# S.net
KiCad netlist of a schematic drawn in Altium Designer
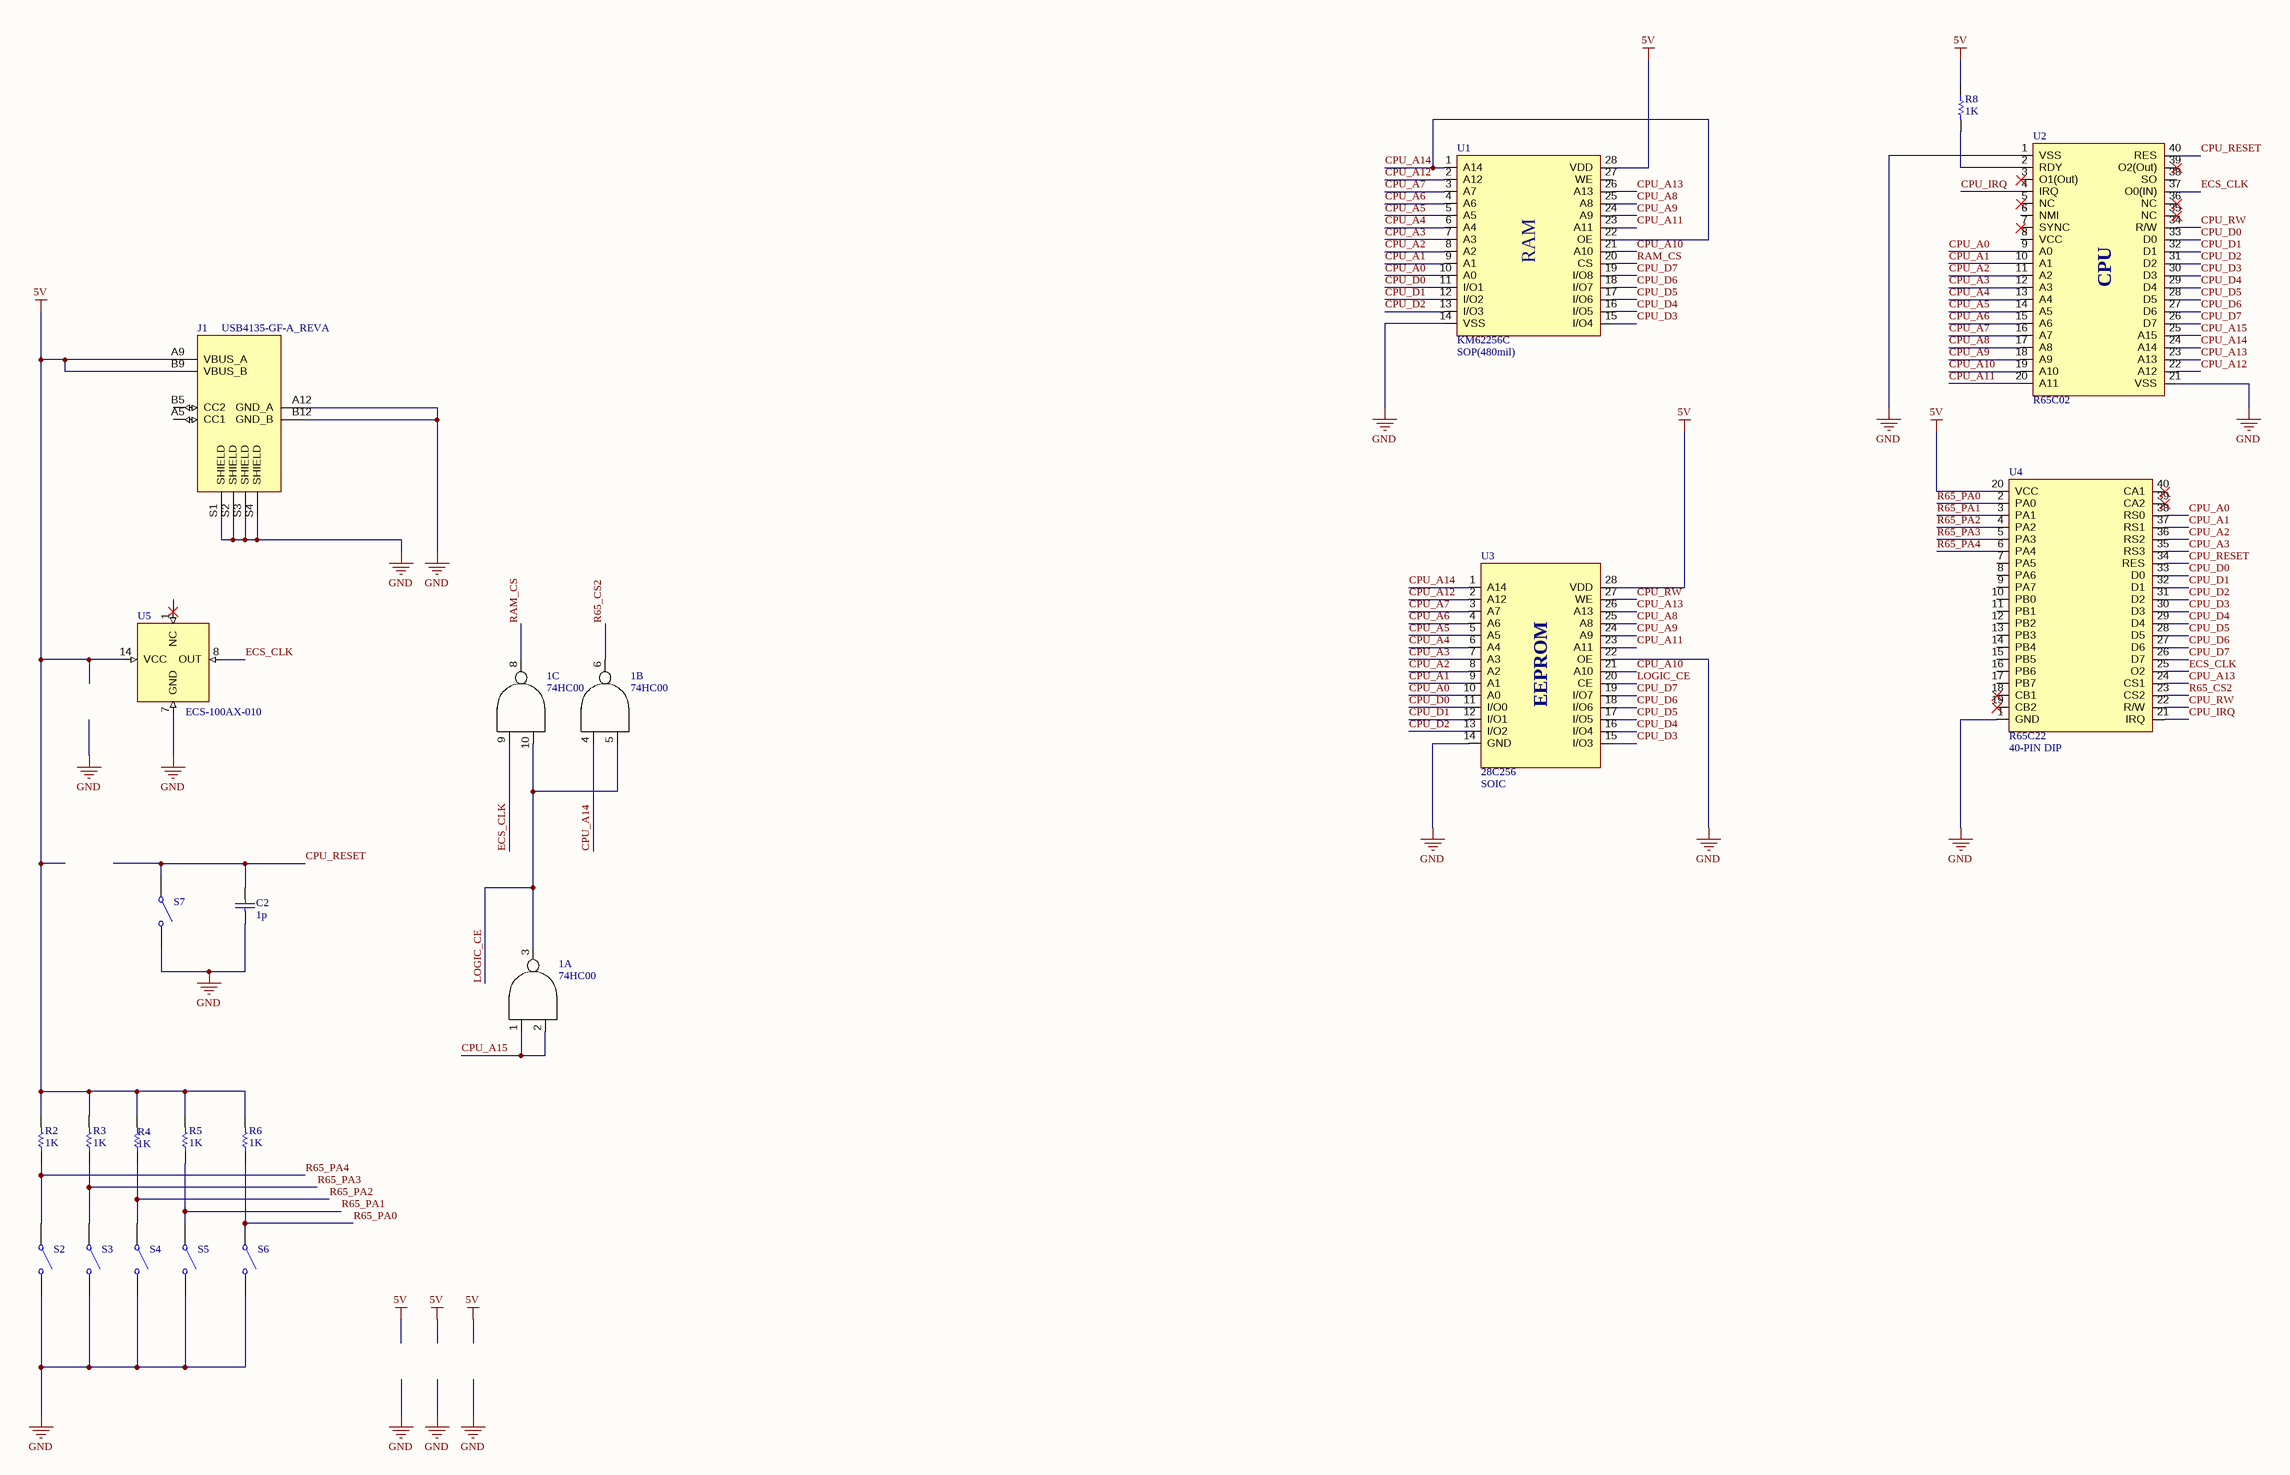
[diagram p0: S.SchDoc]

(export (version "E")
  (design (tool "Eeschema 10.0.6"))
  (components
    (comp (ref "1")
      (value "74HC00")
      (footprint "SOIC127P600X155-14N")
      (description "Quad 2-Input NAND Gate")
      (libsource (lib "") (part "MM74HC00_2"))
    )
    (comp (ref "C2")
      (value "1p")
      (description "Capacitor")
      (libsource (lib "Simulation Generic Components") (part "Capacitor"))
    )
    (comp (ref "J1")
      (value "USB4135-GF-A_REVA")
      (footprint "GCT_USB4135-GF-A_REVA")
      (description "Type C Receptacle, Horizontal, SMT, For Power Charging Only")
      (fields (field (name "MP") "USB4135-GF-A") (field (name "MF") "Global Connector Technology"))
      (libsource (lib "Slib") (part "USB4135-GF-A_REVA"))
    )
    (comp (ref "R2")
      (value "1K")
      (description "Resistor")
      (libsource (lib "Simulation Generic Components") (part "Resistor"))
    )
    (comp (ref "R3")
      (value "1K")
      (description "Resistor")
      (libsource (lib "Simulation Generic Components") (part "Resistor"))
    )
    (comp (ref "R4")
      (value "1K")
      (description "Resistor")
      (libsource (lib "Simulation Generic Components") (part "Resistor"))
    )
    (comp (ref "R5")
      (value "1K")
      (description "Resistor")
      (libsource (lib "Simulation Generic Components") (part "Resistor"))
    )
    (comp (ref "R6")
      (value "1K")
      (description "Resistor")
      (libsource (lib "Simulation Generic Components") (part "Resistor"))
    )
    (comp (ref "R8")
      (value "1K")
      (description "Resistor")
      (libsource (lib "Simulation Generic Components") (part "Resistor"))
    )
    (comp (ref "S2")
      (value "Single-Pole, Single-Throw Switch")
      (libsource (lib "Simulation Generic Components") (part "SPST SW"))
    )
    (comp (ref "S3")
      (value "Single-Pole, Single-Throw Switch")
      (libsource (lib "Simulation Generic Components") (part "SPST SW"))
    )
    (comp (ref "S4")
      (value "Single-Pole, Single-Throw Switch")
      (libsource (lib "Simulation Generic Components") (part "SPST SW"))
    )
    (comp (ref "S5")
      (value "Single-Pole, Single-Throw Switch")
      (libsource (lib "Simulation Generic Components") (part "SPST SW"))
    )
    (comp (ref "S6")
      (value "Single-Pole, Single-Throw Switch")
      (libsource (lib "Simulation Generic Components") (part "SPST SW"))
    )
    (comp (ref "S7")
      (value "Single-Pole, Single-Throw Switch")
      (libsource (lib "Simulation Generic Components") (part "SPST SW"))
    )
    (comp (ref "U1")
      (value "KM62256C")
      (footprint "SOP127P1200X279-28N")
      (description "32Kx8 bit Low Power CMOS Static RAM")
      (fields (field (name "PACKAGE") "SOP(480mil)"))
      (libsource (lib "Slib") (part "62256"))
    )
    (comp (ref "U2")
      (value "R65C02")
      (footprint "SOJ254P1520X356-40N")
      (description "R65C02 family, 5V input, CPU")
      (libsource (lib "Slib") (part "65C02"))
    )
    (comp (ref "U3")
      (value "28C256")
      (footprint "SOIC127P1030X255-28N")
      (description "EEPROM memory; 32kx8bit; 4.5÷5.5V; DIP28; parallel")
      (fields (field (name "PACKAGE") "SOIC"))
      (libsource (lib "Slib") (part "28C256"))
    )
    (comp (ref "U4")
      (value "R65C22")
      (footprint "SOJ254P1520X356-40N")
      (description "8-bit I/O control device")
      (fields (field (name "PACKAGE") "40-PIN DIP"))
      (libsource (lib "Slib") (part "R65C22"))
    )
    (comp (ref "U5")
      (value "ECS-100AX-010")
      (footprint "Oscillator")
      (description "Standard Clock Oscillators DIP-14 5V 1MHz")
      (libsource (lib "Slib") (part "ECS-100AX-010"))
    )
  )
  (nets
    (net (code "1") (name "/CPU_A0") (class "Default")
      (node (ref "U1") (pin "10") (pinfunction "A0_10") (pintype "passive"))
      (node (ref "U2") (pin "9") (pinfunction "A0_9") (pintype "passive"))
      (node (ref "U3") (pin "10") (pinfunction "A0_10") (pintype "passive"))
      (node (ref "U4") (pin "38") (pinfunction "RS0_38") (pintype "passive"))
    )
    (net (code "2") (name "/CPU_A1") (class "Default")
      (node (ref "U1") (pin "9") (pinfunction "A1_9") (pintype "passive"))
      (node (ref "U2") (pin "10") (pinfunction "A1_10") (pintype "passive"))
      (node (ref "U3") (pin "9") (pinfunction "A1_9") (pintype "passive"))
      (node (ref "U4") (pin "37") (pinfunction "RS1_37") (pintype "passive"))
    )
    (net (code "3") (name "/CPU_A2") (class "Default")
      (node (ref "U1") (pin "8") (pinfunction "A2_8") (pintype "passive"))
      (node (ref "U2") (pin "11") (pinfunction "A2_11") (pintype "passive"))
      (node (ref "U3") (pin "8") (pinfunction "A2_8") (pintype "passive"))
      (node (ref "U4") (pin "36") (pinfunction "RS2_36") (pintype "passive"))
    )
    (net (code "4") (name "/CPU_A3") (class "Default")
      (node (ref "U1") (pin "7") (pinfunction "A3_7") (pintype "passive"))
      (node (ref "U2") (pin "12") (pinfunction "A3_12") (pintype "passive"))
      (node (ref "U3") (pin "7") (pinfunction "A3_7") (pintype "passive"))
      (node (ref "U4") (pin "35") (pinfunction "RS3_35") (pintype "passive"))
    )
    (net (code "5") (name "/CPU_A4") (class "Default")
      (node (ref "U1") (pin "6") (pinfunction "A4_6") (pintype "passive"))
      (node (ref "U2") (pin "13") (pinfunction "A4_13") (pintype "passive"))
      (node (ref "U3") (pin "6") (pinfunction "A4_6") (pintype "passive"))
    )
    (net (code "6") (name "/CPU_A5") (class "Default")
      (node (ref "U1") (pin "5") (pinfunction "A5_5") (pintype "passive"))
      (node (ref "U2") (pin "14") (pinfunction "A5_14") (pintype "passive"))
      (node (ref "U3") (pin "5") (pinfunction "A5_5") (pintype "passive"))
    )
    (net (code "7") (name "/CPU_A6") (class "Default")
      (node (ref "U1") (pin "4") (pinfunction "A6_4") (pintype "passive"))
      (node (ref "U2") (pin "15") (pinfunction "A6_15") (pintype "passive"))
      (node (ref "U3") (pin "4") (pinfunction "A6_4") (pintype "passive"))
    )
    (net (code "8") (name "/CPU_A7") (class "Default")
      (node (ref "U1") (pin "3") (pinfunction "A7_3") (pintype "passive"))
      (node (ref "U2") (pin "16") (pinfunction "A7_16") (pintype "passive"))
      (node (ref "U3") (pin "3") (pinfunction "A7_3") (pintype "passive"))
    )
    (net (code "9") (name "/CPU_A8") (class "Default")
      (node (ref "U1") (pin "25") (pinfunction "A8_25") (pintype "passive"))
      (node (ref "U2") (pin "17") (pinfunction "A8_17") (pintype "passive"))
      (node (ref "U3") (pin "25") (pinfunction "A8_25") (pintype "open_emitter"))
    )
    (net (code "10") (name "/CPU_A9") (class "Default")
      (node (ref "U1") (pin "24") (pinfunction "A9_24") (pintype "passive"))
      (node (ref "U2") (pin "18") (pinfunction "A9_18") (pintype "passive"))
      (node (ref "U3") (pin "24") (pinfunction "A9_24") (pintype "open_emitter"))
    )
    (net (code "11") (name "/CPU_A10") (class "Default")
      (node (ref "U1") (pin "21") (pinfunction "A10_21") (pintype "passive"))
      (node (ref "U2") (pin "19") (pinfunction "A10_19") (pintype "passive"))
      (node (ref "U3") (pin "21") (pinfunction "A10_21") (pintype "open_emitter"))
    )
    (net (code "12") (name "/CPU_A11") (class "Default")
      (node (ref "U1") (pin "23") (pinfunction "A11_23") (pintype "passive"))
      (node (ref "U2") (pin "20") (pinfunction "A11_20") (pintype "passive"))
      (node (ref "U3") (pin "23") (pinfunction "A11_23") (pintype "open_emitter"))
    )
    (net (code "13") (name "/CPU_A12") (class "Default")
      (node (ref "U1") (pin "2") (pinfunction "A12_2") (pintype "passive"))
      (node (ref "U2") (pin "22") (pinfunction "A12_22") (pintype "passive"))
      (node (ref "U3") (pin "2") (pinfunction "A12_2") (pintype "passive"))
    )
    (net (code "14") (name "/CPU_A13") (class "Default")
      (node (ref "U1") (pin "26") (pinfunction "A13_26") (pintype "passive"))
      (node (ref "U2") (pin "23") (pinfunction "A13_23") (pintype "passive"))
      (node (ref "U3") (pin "26") (pinfunction "A13_26") (pintype "open_emitter"))
      (node (ref "U4") (pin "24") (pinfunction "CS1_24") (pintype "passive"))
    )
    (net (code "15") (name "/CPU_A14") (class "Default")
      (node (ref "1") (pin "4") (pinfunction "A1_4") (pintype "passive"))
      (node (ref "U1") (pin "1") (pinfunction "A14_1") (pintype "passive"))
      (node (ref "U1") (pin "22") (pinfunction "OE_22") (pintype "passive"))
      (node (ref "U2") (pin "24") (pinfunction "A14_24") (pintype "passive"))
      (node (ref "U3") (pin "1") (pinfunction "A14_1") (pintype "passive"))
    )
    (net (code "16") (name "/CPU_A15") (class "Default")
      (node (ref "1") (pin "1") (pinfunction "A1_1") (pintype "passive"))
      (node (ref "1") (pin "2") (pinfunction "B1_2") (pintype "passive"))
      (node (ref "U2") (pin "25") (pinfunction "A15_25") (pintype "passive"))
    )
    (net (code "17") (name "/CPU_D0") (class "Default")
      (node (ref "U1") (pin "11") (pinfunction "I/O1_11") (pintype "passive"))
      (node (ref "U2") (pin "33") (pinfunction "D0_33") (pintype "passive"))
      (node (ref "U3") (pin "11") (pinfunction "I/O0_11") (pintype "passive"))
      (node (ref "U4") (pin "33") (pinfunction "D0_33") (pintype "passive"))
    )
    (net (code "18") (name "/CPU_D1") (class "Default")
      (node (ref "U1") (pin "12") (pinfunction "I/O2_12") (pintype "passive"))
      (node (ref "U2") (pin "32") (pinfunction "D1_32") (pintype "passive"))
      (node (ref "U3") (pin "12") (pinfunction "I/O1_12") (pintype "passive"))
      (node (ref "U4") (pin "32") (pinfunction "D1_32") (pintype "passive"))
    )
    (net (code "19") (name "/CPU_D2") (class "Default")
      (node (ref "U1") (pin "13") (pinfunction "I/O3_13") (pintype "passive"))
      (node (ref "U2") (pin "31") (pinfunction "D2_31") (pintype "passive"))
      (node (ref "U3") (pin "13") (pinfunction "I/O2_13") (pintype "passive"))
      (node (ref "U4") (pin "31") (pinfunction "D2_31") (pintype "passive"))
    )
    (net (code "20") (name "/CPU_D3") (class "Default")
      (node (ref "U1") (pin "15") (pinfunction "I/O4_15") (pintype "passive"))
      (node (ref "U2") (pin "30") (pinfunction "D3_30") (pintype "passive"))
      (node (ref "U3") (pin "15") (pinfunction "I/O3_15") (pintype "open_emitter"))
      (node (ref "U4") (pin "30") (pinfunction "D3_30") (pintype "passive"))
    )
    (net (code "21") (name "/CPU_D4") (class "Default")
      (node (ref "U1") (pin "16") (pinfunction "I/O5_16") (pintype "passive"))
      (node (ref "U2") (pin "29") (pinfunction "D4_29") (pintype "passive"))
      (node (ref "U3") (pin "16") (pinfunction "I/O4_16") (pintype "open_emitter"))
      (node (ref "U4") (pin "29") (pinfunction "D4_29") (pintype "passive"))
    )
    (net (code "22") (name "/CPU_D5") (class "Default")
      (node (ref "U1") (pin "17") (pinfunction "I/O6_17") (pintype "passive"))
      (node (ref "U2") (pin "28") (pinfunction "D5_28") (pintype "passive"))
      (node (ref "U3") (pin "17") (pinfunction "I/O5_17") (pintype "open_emitter"))
      (node (ref "U4") (pin "28") (pinfunction "D5_28") (pintype "passive"))
    )
    (net (code "23") (name "/CPU_D6") (class "Default")
      (node (ref "U1") (pin "18") (pinfunction "I/O7_18") (pintype "passive"))
      (node (ref "U2") (pin "27") (pinfunction "D6_27") (pintype "passive"))
      (node (ref "U3") (pin "18") (pinfunction "I/O6_18") (pintype "open_emitter"))
      (node (ref "U4") (pin "27") (pinfunction "D6_27") (pintype "passive"))
    )
    (net (code "24") (name "/CPU_D7") (class "Default")
      (node (ref "U1") (pin "19") (pinfunction "I/O8_19") (pintype "passive"))
      (node (ref "U2") (pin "26") (pinfunction "D7_26") (pintype "passive"))
      (node (ref "U3") (pin "19") (pinfunction "I/O7_19") (pintype "open_emitter"))
      (node (ref "U4") (pin "26") (pinfunction "D7_26") (pintype "passive"))
    )
    (net (code "25") (name "/CPU_IRQ") (class "Default")
      (node (ref "U2") (pin "4") (pinfunction "IRQ_4") (pintype "passive"))
      (node (ref "U4") (pin "21") (pinfunction "IRQ_21") (pintype "passive"))
    )
    (net (code "26") (name "/CPU_RESET") (class "Default")
      (node (ref "C2") (pin "2") (pinfunction "2_2") (pintype "passive"))
      (node (ref "S7") (pin "1") (pinfunction "1_1") (pintype "passive"))
      (node (ref "U2") (pin "40") (pinfunction "RES_40") (pintype "passive"))
      (node (ref "U4") (pin "34") (pinfunction "RES_34") (pintype "passive"))
    )
    (net (code "27") (name "/CPU_RW") (class "Default")
      (node (ref "U2") (pin "34") (pinfunction "R/W_34") (pintype "passive"))
      (node (ref "U3") (pin "27") (pinfunction "WE_27") (pintype "open_emitter"))
      (node (ref "U4") (pin "22") (pinfunction "R/W_22") (pintype "passive"))
    )
    (net (code "28") (name "/ECS_CLK") (class "Default")
      (node (ref "1") (pin "9") (pinfunction "A1_9") (pintype "passive"))
      (node (ref "U2") (pin "37") (pinfunction "O0(IN)_37") (pintype "passive"))
      (node (ref "U4") (pin "25") (pinfunction "O2_25") (pintype "passive"))
      (node (ref "U5") (pin "8") (pinfunction "OUT_8") (pintype "input"))
    )
    (net (code "29") (name "/LOGIC_CE") (class "Default")
      (node (ref "1") (pin "10") (pinfunction "B1_10") (pintype "passive"))
      (node (ref "1") (pin "3") (pinfunction "Y2_3") (pintype "passive"))
      (node (ref "1") (pin "5") (pinfunction "B1_5") (pintype "passive"))
      (node (ref "U3") (pin "20") (pinfunction "CE_20") (pintype "open_emitter"))
    )
    (net (code "30") (name "/R65_CS2") (class "Default")
      (node (ref "1") (pin "6") (pinfunction "Y2_6") (pintype "passive"))
      (node (ref "U4") (pin "23") (pinfunction "CS2_23") (pintype "passive"))
    )
    (net (code "31") (name "/R65_PA0") (class "Default")
      (node (ref "R6") (pin "1") (pinfunction "1_1") (pintype "passive"))
      (node (ref "S6") (pin "1") (pinfunction "1_1") (pintype "passive"))
      (node (ref "U4") (pin "2") (pinfunction "PA0_2") (pintype "passive"))
    )
    (net (code "32") (name "/R65_PA1") (class "Default")
      (node (ref "R5") (pin "1") (pinfunction "1_1") (pintype "passive"))
      (node (ref "S5") (pin "1") (pinfunction "1_1") (pintype "passive"))
      (node (ref "U4") (pin "3") (pinfunction "PA1_3") (pintype "passive"))
    )
    (net (code "33") (name "/R65_PA2") (class "Default")
      (node (ref "R4") (pin "1") (pinfunction "1_1") (pintype "passive"))
      (node (ref "S4") (pin "1") (pinfunction "1_1") (pintype "passive"))
      (node (ref "U4") (pin "4") (pinfunction "PA2_4") (pintype "passive"))
    )
    (net (code "34") (name "/R65_PA3") (class "Default")
      (node (ref "R3") (pin "1") (pinfunction "1_1") (pintype "passive"))
      (node (ref "S3") (pin "1") (pinfunction "1_1") (pintype "passive"))
      (node (ref "U4") (pin "5") (pinfunction "PA3_5") (pintype "passive"))
    )
    (net (code "35") (name "/R65_PA4") (class "Default")
      (node (ref "R2") (pin "1") (pinfunction "1_1") (pintype "passive"))
      (node (ref "S2") (pin "1") (pinfunction "1_1") (pintype "passive"))
      (node (ref "U4") (pin "6") (pinfunction "PA4_6") (pintype "passive"))
    )
    (net (code "36") (name "/RAM_CS") (class "Default")
      (node (ref "1") (pin "8") (pinfunction "Y2_8") (pintype "passive"))
      (node (ref "U1") (pin "20") (pinfunction "CS_20") (pintype "passive"))
    )
    (net (code "37") (name "5V") (class "Default")
      (node (ref "J1") (pin "A9") (pinfunction "VBUS_A_A9") (pintype "power_in"))
      (node (ref "J1") (pin "B9") (pinfunction "VBUS_B_B9") (pintype "power_in"))
      (node (ref "R2") (pin "2") (pinfunction "2_2") (pintype "passive"))
      (node (ref "R3") (pin "2") (pinfunction "2_2") (pintype "passive"))
      (node (ref "R4") (pin "2") (pinfunction "2_2") (pintype "passive"))
      (node (ref "R5") (pin "2") (pinfunction "2_2") (pintype "passive"))
      (node (ref "R6") (pin "2") (pinfunction "2_2") (pintype "passive"))
      (node (ref "R8") (pin "1") (pinfunction "1_1") (pintype "passive"))
      (node (ref "U1") (pin "28") (pinfunction "VDD_28") (pintype "passive"))
      (node (ref "U3") (pin "28") (pinfunction "VDD_28") (pintype "open_emitter"))
      (node (ref "U4") (pin "20") (pinfunction "VCC_20") (pintype "passive"))
      (node (ref "U5") (pin "14") (pinfunction "VCC_14") (pintype "input"))
    )
    (net (code "38") (name "GND") (class "Default")
      (node (ref "C2") (pin "1") (pinfunction "1_1") (pintype "passive"))
      (node (ref "J1") (pin "A12") (pinfunction "GND_A_A12") (pintype "power_in"))
      (node (ref "J1") (pin "B12") (pinfunction "GND_B_B12") (pintype "power_in"))
      (node (ref "J1") (pin "S1") (pinfunction "SHIELD_S1") (pintype "passive"))
      (node (ref "J1") (pin "S2") (pinfunction "SHIELD_S2") (pintype "passive"))
      (node (ref "J1") (pin "S3") (pinfunction "SHIELD_S3") (pintype "passive"))
      (node (ref "J1") (pin "S4") (pinfunction "SHIELD_S4") (pintype "passive"))
      (node (ref "S2") (pin "2") (pinfunction "2_2") (pintype "passive"))
      (node (ref "S3") (pin "2") (pinfunction "2_2") (pintype "passive"))
      (node (ref "S4") (pin "2") (pinfunction "2_2") (pintype "passive"))
      (node (ref "S5") (pin "2") (pinfunction "2_2") (pintype "passive"))
      (node (ref "S6") (pin "2") (pinfunction "2_2") (pintype "passive"))
      (node (ref "S7") (pin "2") (pinfunction "2_2") (pintype "passive"))
      (node (ref "U1") (pin "14") (pinfunction "VSS_14") (pintype "passive"))
      (node (ref "U2") (pin "1") (pinfunction "VSS_1") (pintype "passive"))
      (node (ref "U2") (pin "21") (pinfunction "VSS_21") (pintype "passive"))
      (node (ref "U3") (pin "14") (pinfunction "GND_14") (pintype "passive"))
      (node (ref "U3") (pin "22") (pinfunction "OE_22") (pintype "open_emitter"))
      (node (ref "U4") (pin "1") (pinfunction "GND_1") (pintype "passive"))
      (node (ref "U5") (pin "7") (pinfunction "GND_7") (pintype "input"))
    )
    (net (code "39") (name "Net-(U2-RDY)") (class "Default")
      (node (ref "R8") (pin "2") (pinfunction "2_2") (pintype "passive"))
      (node (ref "U2") (pin "2") (pinfunction "RDY_2") (pintype "passive"))
    )
    (net (code "40") (name "unconnected-(J1-CC1-PadA5)") (class "Default")
      (node (ref "J1") (pin "A5") (pinfunction "CC1_A5") (pintype "bidirectional"))
    )
    (net (code "41") (name "unconnected-(J1-CC2-PadB5)") (class "Default")
      (node (ref "J1") (pin "B5") (pinfunction "CC2_B5") (pintype "bidirectional"))
    )
    (net (code "42") (name "unconnected-(U1-WE-Pad27)") (class "Default")
      (node (ref "U1") (pin "27") (pinfunction "WE_27") (pintype "passive"))
    )
    (net (code "43") (name "unconnected-(U2-NC-Pad5)") (class "Default")
      (node (ref "U2") (pin "5") (pinfunction "NC_5") (pintype "passive+no_connect"))
    )
    (net (code "44") (name "unconnected-(U2-NC-Pad35)") (class "Default")
      (node (ref "U2") (pin "35") (pinfunction "NC_35") (pintype "passive+no_connect"))
    )
    (net (code "45") (name "unconnected-(U2-NC-Pad36)") (class "Default")
      (node (ref "U2") (pin "36") (pinfunction "NC_36") (pintype "passive+no_connect"))
    )
    (net (code "46") (name "unconnected-(U2-NMI-Pad6)") (class "Default")
      (node (ref "U2") (pin "6") (pinfunction "NMI_6") (pintype "passive"))
    )
    (net (code "47") (name "unconnected-(U2-O1(Out)-Pad3)") (class "Default")
      (node (ref "U2") (pin "3") (pinfunction "O1(Out)_3") (pintype "passive+no_connect"))
    )
    (net (code "48") (name "unconnected-(U2-O2(Out)-Pad39)") (class "Default")
      (node (ref "U2") (pin "39") (pinfunction "O2(Out)_39") (pintype "passive+no_connect"))
    )
    (net (code "49") (name "unconnected-(U2-SO-Pad38)") (class "Default")
      (node (ref "U2") (pin "38") (pinfunction "SO_38") (pintype "passive"))
    )
    (net (code "50") (name "unconnected-(U2-SYNC-Pad7)") (class "Default")
      (node (ref "U2") (pin "7") (pinfunction "SYNC_7") (pintype "passive+no_connect"))
    )
    (net (code "51") (name "unconnected-(U2-VCC-Pad8)") (class "Default")
      (node (ref "U2") (pin "8") (pinfunction "VCC_8") (pintype "passive"))
    )
    (net (code "52") (name "unconnected-(U4-CA1-Pad40)") (class "Default")
      (node (ref "U4") (pin "40") (pinfunction "CA1_40") (pintype "passive+no_connect"))
    )
    (net (code "53") (name "unconnected-(U4-CA2-Pad39)") (class "Default")
      (node (ref "U4") (pin "39") (pinfunction "CA2_39") (pintype "passive+no_connect"))
    )
    (net (code "54") (name "unconnected-(U4-CB1-Pad18)") (class "Default")
      (node (ref "U4") (pin "18") (pinfunction "CB1_18") (pintype "passive+no_connect"))
    )
    (net (code "55") (name "unconnected-(U4-CB2-Pad19)") (class "Default")
      (node (ref "U4") (pin "19") (pinfunction "CB2_19") (pintype "passive+no_connect"))
    )
    (net (code "56") (name "unconnected-(U4-PA5-Pad7)") (class "Default")
      (node (ref "U4") (pin "7") (pinfunction "PA5_7") (pintype "passive"))
    )
    (net (code "57") (name "unconnected-(U4-PA6-Pad8)") (class "Default")
      (node (ref "U4") (pin "8") (pinfunction "PA6_8") (pintype "passive"))
    )
    (net (code "58") (name "unconnected-(U4-PA7-Pad9)") (class "Default")
      (node (ref "U4") (pin "9") (pinfunction "PA7_9") (pintype "passive"))
    )
    (net (code "59") (name "unconnected-(U4-PB0-Pad10)") (class "Default")
      (node (ref "U4") (pin "10") (pinfunction "PB0_10") (pintype "passive"))
    )
    (net (code "60") (name "unconnected-(U4-PB1-Pad11)") (class "Default")
      (node (ref "U4") (pin "11") (pinfunction "PB1_11") (pintype "passive"))
    )
    (net (code "61") (name "unconnected-(U4-PB2-Pad12)") (class "Default")
      (node (ref "U4") (pin "12") (pinfunction "PB2_12") (pintype "passive"))
    )
    (net (code "62") (name "unconnected-(U4-PB3-Pad13)") (class "Default")
      (node (ref "U4") (pin "13") (pinfunction "PB3_13") (pintype "passive"))
    )
    (net (code "63") (name "unconnected-(U4-PB4-Pad14)") (class "Default")
      (node (ref "U4") (pin "14") (pinfunction "PB4_14") (pintype "passive"))
    )
    (net (code "64") (name "unconnected-(U4-PB5-Pad15)") (class "Default")
      (node (ref "U4") (pin "15") (pinfunction "PB5_15") (pintype "passive"))
    )
    (net (code "65") (name "unconnected-(U4-PB6-Pad16)") (class "Default")
      (node (ref "U4") (pin "16") (pinfunction "PB6_16") (pintype "passive"))
    )
    (net (code "66") (name "unconnected-(U4-PB7-Pad17)") (class "Default")
      (node (ref "U4") (pin "17") (pinfunction "PB7_17") (pintype "passive"))
    )
    (net (code "67") (name "unconnected-(U5-NC-Pad1)") (class "Default")
      (node (ref "U5") (pin "1") (pinfunction "NC_1") (pintype "input+no_connect"))
    )
  )
)
